# EthernetGCS.net
KiCad netlist of a schematic drawn in EAGLE
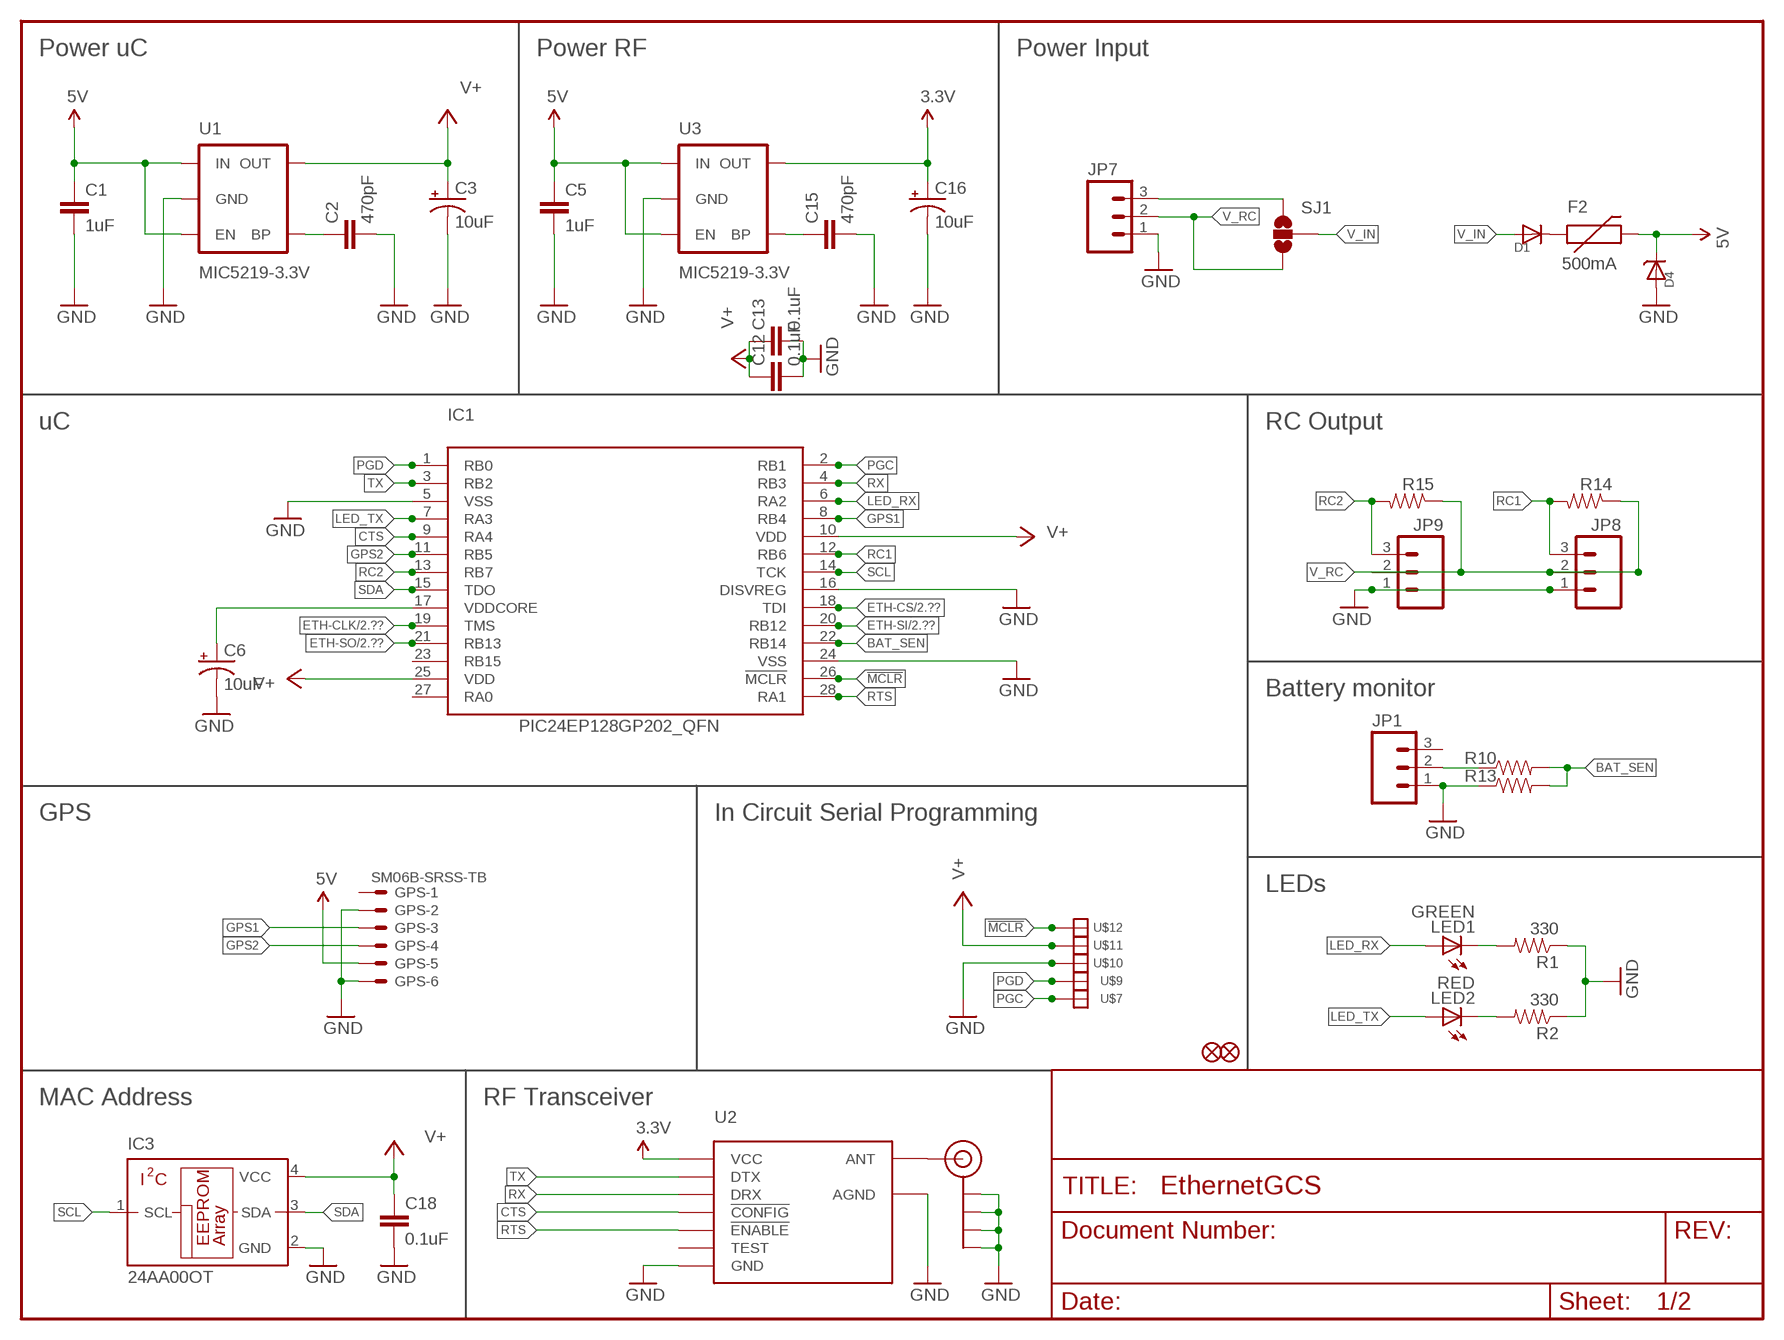
[diagram p0: schematic, sheet 1]
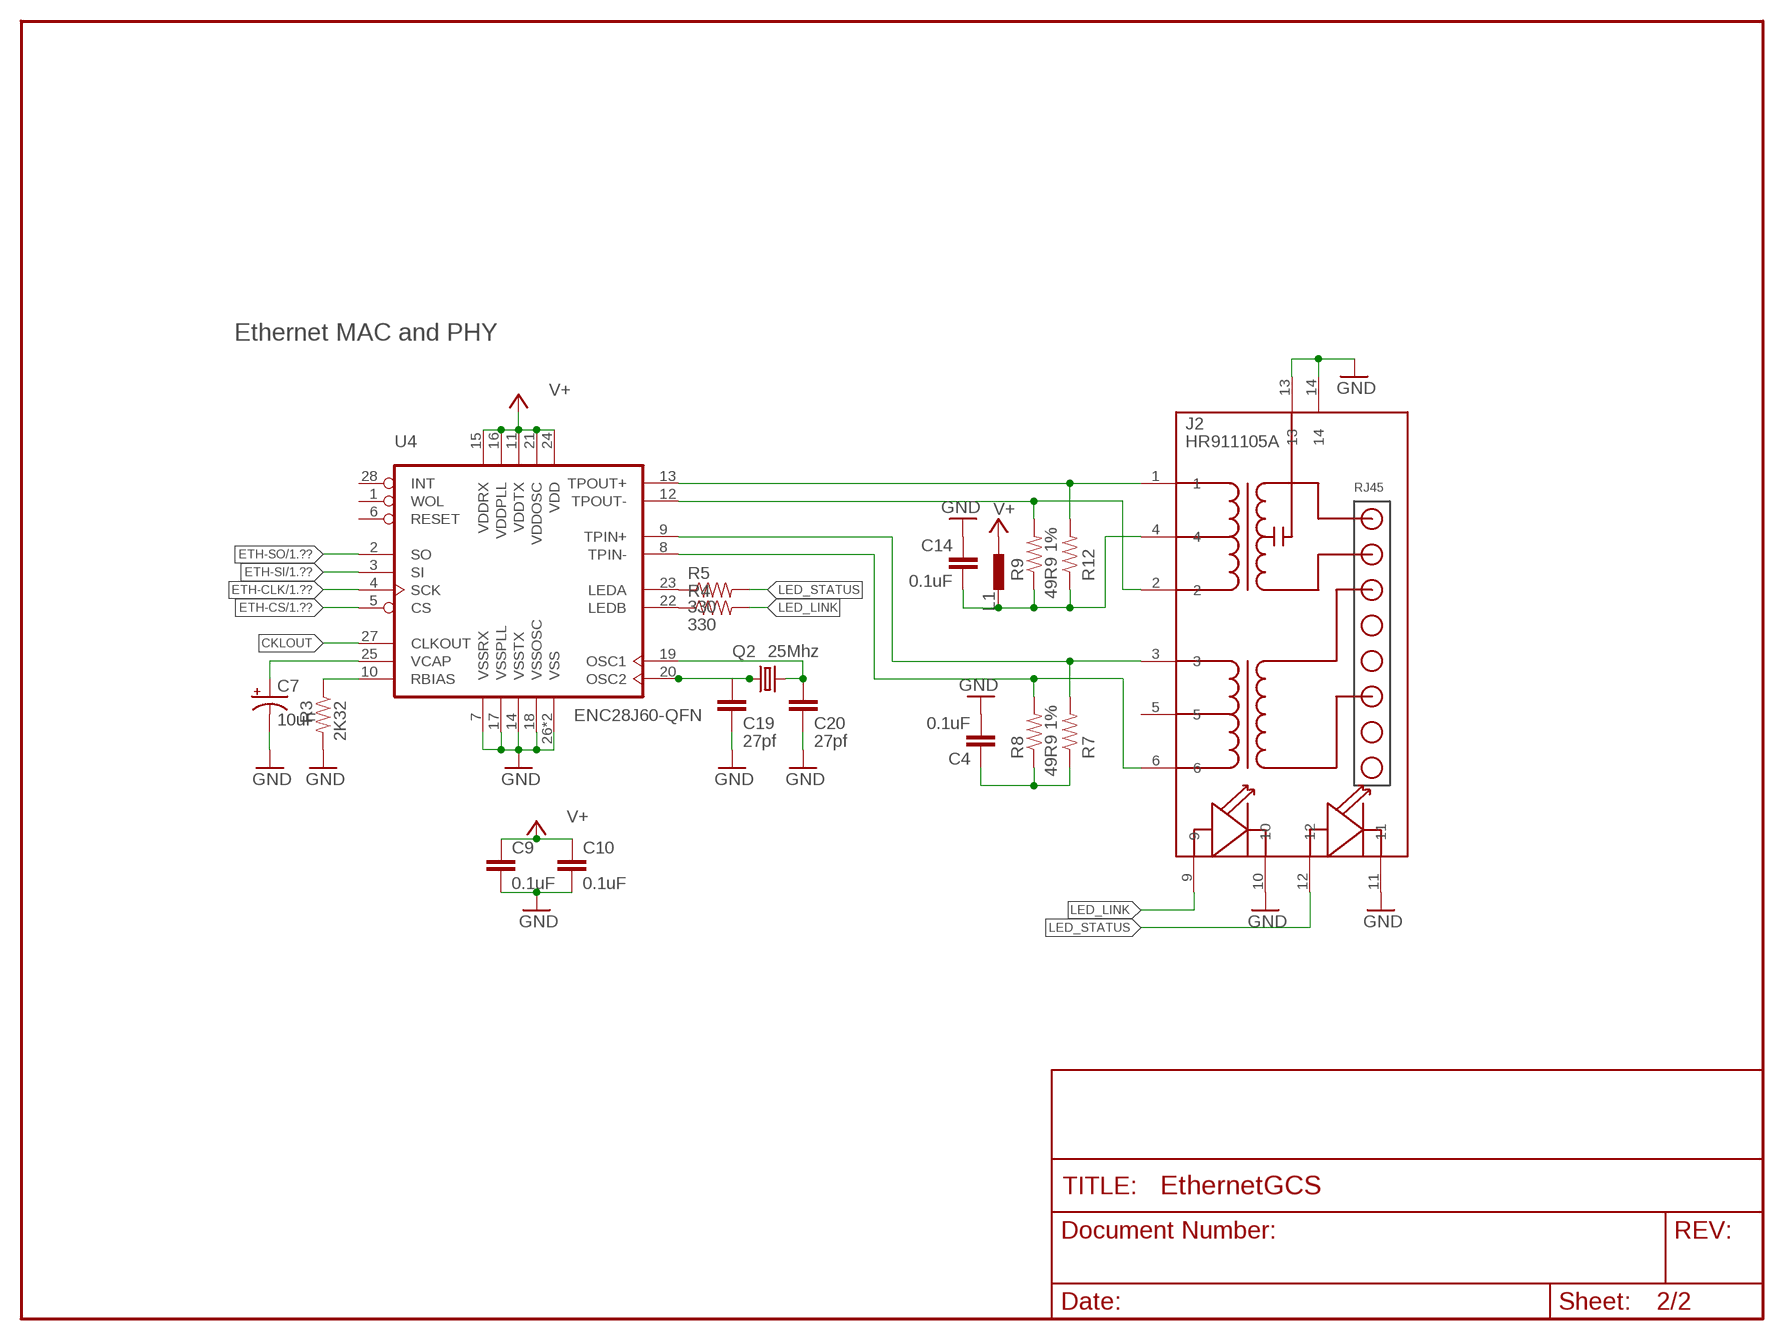
[diagram p1: schematic, sheet 2]

(export (version "E")
  (design (tool "Eeschema 10.0.6"))
  (components
    (comp (ref "C1")
      (value "1uF")
      (footprint "eagle-import:0402-CAP")
      (libsource (lib "eagle-import") (part "CAP0402-CAP"))
    )
    (comp (ref "C2")
      (value "470pF")
      (footprint "eagle-import:0402-CAP")
      (libsource (lib "eagle-import") (part "CAP0402-CAP"))
    )
    (comp (ref "C3")
      (value "10uF")
      (footprint "eagle-import:EIA3216")
      (libsource (lib "eagle-import") (part "CAP_POL1206"))
    )
    (comp (ref "C5")
      (value "1uF")
      (footprint "eagle-import:0402-CAP")
      (libsource (lib "eagle-import") (part "CAP0402-CAP"))
    )
    (comp (ref "C6")
      (value "10uF")
      (footprint "eagle-import:EIA3216")
      (libsource (lib "eagle-import") (part "CAP_POL1206"))
    )
    (comp (ref "C12")
      (value "0.1uF")
      (footprint "eagle-import:0402-CAP")
      (libsource (lib "eagle-import") (part "CAP0402-CAP"))
    )
    (comp (ref "C13")
      (value "0.1uF")
      (footprint "eagle-import:0402-CAP")
      (libsource (lib "eagle-import") (part "CAP0402-CAP"))
    )
    (comp (ref "C15")
      (value "470pF")
      (footprint "eagle-import:0402-CAP")
      (libsource (lib "eagle-import") (part "CAP0402-CAP"))
    )
    (comp (ref "C16")
      (value "10uF")
      (footprint "eagle-import:EIA3216")
      (libsource (lib "eagle-import") (part "CAP_POL1206"))
    )
    (comp (ref "C18")
      (value "0.1uF")
      (footprint "eagle-import:0402-CAP")
      (libsource (lib "eagle-import") (part "CAP0402-CAP"))
    )
    (comp (ref "D1")
      (value "MBR120VLSFT1G")
      (footprint "eagle-import:SOD-123")
      (libsource (lib "eagle-import") (part "DIODESOD-123"))
    )
    (comp (ref "D4")
      (value "MMSZ5233BT1G")
      (footprint "eagle-import:SOD-123")
      (libsource (lib "eagle-import") (part "DIODESOD-123"))
    )
    (comp (ref "F2")
      (value "500mA")
      (footprint "eagle-import:PTC-1206")
      (libsource (lib "eagle-import") (part "PTCSMD"))
    )
    (comp (ref "GPS")
      (value "SM06B-SRSS-TB")
      (footprint "eagle-import:SM06B-SRSS-TB")
      (libsource (lib "eagle-import") (part "?M06B-SRSS-TBS"))
    )
    (comp (ref "IC1")
      (value "PIC24EP128GP202_QFN")
      (footprint "eagle-import:QFN28-ML_6X6MM")
      (fields
        (field (name "MPN") "PIC24FJ64GA002-E/ML")
        (field (name "MPN_1") "PIC24FJ64GA002-E/ML")
        (field (name "OC_FARNELL") "1818728")
        (field (name "OC_NEWARK") "98M1922")
      )
      (libsource (lib "eagle-import") (part "PIC24FJ64GA002_QFN"))
    )
    (comp (ref "IC3")
      (value "24AA00OT")
      (footprint "eagle-import:SOT23-5L")
      (fields (field (name "MF") "MICROCHIP") (field (name "MPN") "24AA00T-I/OTG"))
      (libsource (lib "eagle-import") (part "2400OTAA"))
    )
    (comp (ref "J$1")
      (value "SMA_EDGE")
      (footprint "eagle-import:SMA-EDGE")
      (libsource (lib "eagle-import") (part "SMA_EDGE"))
    )
    (comp (ref "JP1")
      (value "M03PTH")
      (footprint "eagle-import:1X03")
      (libsource (lib "eagle-import") (part "M03PTH"))
    )
    (comp (ref "JP2")
      (value "FIDUCIAL1X2")
      (footprint "eagle-import:FIDUCIAL-1X2")
      (libsource (lib "eagle-import") (part "FIDUCIAL1X2"))
    )
    (comp (ref "JP3")
      (value "FIDUCIAL1X2")
      (footprint "eagle-import:FIDUCIAL-1X2")
      (libsource (lib "eagle-import") (part "FIDUCIAL1X2"))
    )
    (comp (ref "JP7")
      (value "M03PTH")
      (footprint "eagle-import:1X03")
      (libsource (lib "eagle-import") (part "M03PTH"))
    )
    (comp (ref "JP8")
      (value "M03PTH")
      (footprint "eagle-import:1X03")
      (libsource (lib "eagle-import") (part "M03PTH"))
    )
    (comp (ref "JP9")
      (value "M03PTH")
      (footprint "eagle-import:1X03")
      (libsource (lib "eagle-import") (part "M03PTH"))
    )
    (comp (ref "LED1")
      (value "GREEN")
      (footprint "eagle-import:LED-0603")
      (libsource (lib "eagle-import") (part "LED0603"))
    )
    (comp (ref "LED2")
      (value "RED")
      (footprint "eagle-import:LED-0603")
      (libsource (lib "eagle-import") (part "LED0603"))
    )
    (comp (ref "R1")
      (value "330")
      (footprint "eagle-import:0402-RES")
      (libsource (lib "eagle-import") (part "RESISTOR0402-RES"))
    )
    (comp (ref "R2")
      (value "330")
      (footprint "eagle-import:0402-RES")
      (libsource (lib "eagle-import") (part "RESISTOR0402-RES"))
    )
    (comp (ref "R10")
      (value "RESISTOR0402-RES")
      (footprint "eagle-import:0402-RES")
      (libsource (lib "eagle-import") (part "RESISTOR0402-RES"))
    )
    (comp (ref "R13")
      (value "RESISTOR0402-RES")
      (footprint "eagle-import:0402-RES")
      (libsource (lib "eagle-import") (part "RESISTOR0402-RES"))
    )
    (comp (ref "R14")
      (value "RESISTOR0402-RES")
      (footprint "eagle-import:0402-RES")
      (libsource (lib "eagle-import") (part "RESISTOR0402-RES"))
    )
    (comp (ref "R15")
      (value "RESISTOR0402-RES")
      (footprint "eagle-import:0402-RES")
      (libsource (lib "eagle-import") (part "RESISTOR0402-RES"))
    )
    (comp (ref "SJ1")
      (value "SOLDERJUMPER_2WAYT")
      (footprint "eagle-import:SJ_2")
      (libsource (lib "eagle-import") (part "SOLDERJUMPER_2WAYT"))
    )
    (comp (ref "U$7")
      (value "SOLDER_PAD150_75")
      (footprint "eagle-import:SOLD_PAD_150_75")
      (libsource (lib "eagle-import") (part "SOLDER_PAD150_75"))
    )
    (comp (ref "U$9")
      (value "SOLDER_PAD150_75")
      (footprint "eagle-import:SOLD_PAD_150_75")
      (libsource (lib "eagle-import") (part "SOLDER_PAD150_75"))
    )
    (comp (ref "U$10")
      (value "SOLDER_PAD150_75")
      (footprint "eagle-import:SOLD_PAD_150_75")
      (libsource (lib "eagle-import") (part "SOLDER_PAD150_75"))
    )
    (comp (ref "U$11")
      (value "SOLDER_PAD150_75")
      (footprint "eagle-import:SOLD_PAD_150_75")
      (libsource (lib "eagle-import") (part "SOLDER_PAD150_75"))
    )
    (comp (ref "U$12")
      (value "SOLDER_PAD150_75")
      (footprint "eagle-import:SOLD_PAD_150_75")
      (libsource (lib "eagle-import") (part "SOLDER_PAD150_75"))
    )
    (comp (ref "U1")
      (value "MIC5219-3.3V")
      (footprint "eagle-import:SOT23-5")
      (libsource (lib "eagle-import") (part "V_REG_LDOSMD"))
    )
    (comp (ref "U2")
      (value "HM-TRPSMD")
      (footprint "eagle-import:HM-TRP-SMD")
      (libsource (lib "eagle-import") (part "HM-TRPSMD"))
    )
    (comp (ref "U3")
      (value "MIC5219-3.3V")
      (footprint "eagle-import:SOT23-5")
      (libsource (lib "eagle-import") (part "V_REG_LDOSMD"))
    )
    (comp (ref "C4")
      (value "0.1uF")
      (footprint "eagle-import:0402-CAP")
      (libsource (lib "eagle-import") (part "CAP0402-CAP"))
    )
    (comp (ref "C7")
      (value "10uF")
      (footprint "eagle-import:EIA3216")
      (libsource (lib "eagle-import") (part "CAP_POL1206"))
    )
    (comp (ref "C9")
      (value "0.1uF")
      (footprint "eagle-import:0402-CAP")
      (libsource (lib "eagle-import") (part "CAP0402-CAP"))
    )
    (comp (ref "C10")
      (value "0.1uF")
      (footprint "eagle-import:0402-CAP")
      (libsource (lib "eagle-import") (part "CAP0402-CAP"))
    )
    (comp (ref "C14")
      (value "0.1uF")
      (footprint "eagle-import:0402-CAP")
      (libsource (lib "eagle-import") (part "CAP0402-CAP"))
    )
    (comp (ref "C19")
      (value "27pf")
      (footprint "eagle-import:0402-CAP")
      (libsource (lib "eagle-import") (part "CAP0402-CAP"))
    )
    (comp (ref "C20")
      (value "27pf")
      (footprint "eagle-import:0402-CAP")
      (libsource (lib "eagle-import") (part "CAP0402-CAP"))
    )
    (comp (ref "J2")
      (value "HR911105A")
      (footprint "eagle-import:HR911105A")
      (libsource (lib "eagle-import") (part "HR911105A"))
    )
    (comp (ref "L1")
      (value "BLM15HD102SN1")
      (footprint "eagle-import:0402-IND")
      (libsource (lib "eagle-import") (part "INDUCTOR-0402"))
    )
    (comp (ref "Q2")
      (value "25Mhz")
      (footprint "eagle-import:CTS406")
      (libsource (lib "eagle-import") (part "CRYSTALCTS406"))
    )
    (comp (ref "R3")
      (value "2K32")
      (footprint "eagle-import:0402-RES")
      (libsource (lib "eagle-import") (part "RESISTOR0402-RES"))
    )
    (comp (ref "R4")
      (value "330")
      (footprint "eagle-import:0402-RES")
      (libsource (lib "eagle-import") (part "RESISTOR0402-RES"))
    )
    (comp (ref "R5")
      (value "330")
      (footprint "eagle-import:0402-RES")
      (libsource (lib "eagle-import") (part "RESISTOR0402-RES"))
    )
    (comp (ref "R7")
      (value "49R9 1%")
      (footprint "eagle-import:0402-RES")
      (libsource (lib "eagle-import") (part "RESISTOR0402-RES"))
    )
    (comp (ref "R8")
      (value "49R9 1%")
      (footprint "eagle-import:0402-RES")
      (libsource (lib "eagle-import") (part "RESISTOR0402-RES"))
    )
    (comp (ref "R9")
      (value "49R9 1%")
      (footprint "eagle-import:0402-RES")
      (libsource (lib "eagle-import") (part "RESISTOR0402-RES"))
    )
    (comp (ref "R12")
      (value "49R9 1%")
      (footprint "eagle-import:0402-RES")
      (libsource (lib "eagle-import") (part "RESISTOR0402-RES"))
    )
    (comp (ref "U4")
      (value "ENC28J60-QFN")
      (footprint "eagle-import:QFN28")
      (libsource (lib "eagle-import") (part "ENC28J60-QFN"))
    )
  )
  (nets
    (net (code "1") (name "3.3V") (class "Default")
      (node (ref "C16") (pin "A") (pinfunction "+_A") (pintype "passive"))
      (node (ref "U2") (pin "VCC") (pinfunction "VCC_VCC") (pintype "power_in"))
      (node (ref "U3") (pin "5") (pinfunction "OUT_5") (pintype "passive"))
    )
    (net (code "2") (name "5V") (class "Default")
      (node (ref "C1") (pin "1") (pinfunction "1_1") (pintype "passive"))
      (node (ref "C5") (pin "1") (pinfunction "1_1") (pintype "passive"))
      (node (ref "D4") (pin "C") (pinfunction "C_C") (pintype "passive"))
      (node (ref "F2") (pin "2") (pinfunction "2_2") (pintype "bidirectional"))
      (node (ref "GPS") (pin "5") (pinfunction "S_5") (pintype "passive"))
      (node (ref "U1") (pin "1") (pinfunction "IN_1") (pintype "input"))
      (node (ref "U1") (pin "3") (pinfunction "EN_3") (pintype "input"))
      (node (ref "U3") (pin "1") (pinfunction "IN_1") (pintype "input"))
      (node (ref "U3") (pin "3") (pinfunction "EN_3") (pintype "input"))
    )
    (net (code "3") (name "BAT_SEN") (class "Default")
      (node (ref "IC1") (pin "22") (pinfunction "RB14_22") (pintype "bidirectional"))
      (node (ref "R10") (pin "2") (pinfunction "2_2") (pintype "passive"))
      (node (ref "R13") (pin "2") (pinfunction "2_2") (pintype "passive"))
    )
    (net (code "4") (name "CKLOUT") (class "Default")
      (node (ref "U4") (pin "27") (pinfunction "CLKOUT_27") (pintype "output"))
    )
    (net (code "5") (name "CTS") (class "Default")
      (node (ref "IC1") (pin "9") (pinfunction "RA4_9") (pintype "bidirectional"))
      (node (ref "U2") (pin "!CONFIG") (pinfunction "~{CONFIG}_!CONFIG") (pintype "input"))
    )
    (net (code "6") (name "ETH-CLK") (class "Default")
      (node (ref "IC1") (pin "19") (pinfunction "TMS_19") (pintype "input"))
      (node (ref "U4") (pin "4") (pinfunction "SCK_4") (pintype "input"))
    )
    (net (code "7") (name "ETH-CS") (class "Default")
      (node (ref "IC1") (pin "18") (pinfunction "TDI_18") (pintype "input"))
      (node (ref "U4") (pin "5") (pinfunction "CS_5") (pintype "input"))
    )
    (net (code "8") (name "ETH-SI") (class "Default")
      (node (ref "IC1") (pin "20") (pinfunction "RB12_20") (pintype "bidirectional"))
      (node (ref "U4") (pin "3") (pinfunction "SI_3") (pintype "input"))
    )
    (net (code "9") (name "ETH-SO") (class "Default")
      (node (ref "IC1") (pin "21") (pinfunction "RB13_21") (pintype "bidirectional"))
      (node (ref "U4") (pin "2") (pinfunction "SO_2") (pintype "output"))
    )
    (net (code "10") (name "GND") (class "Default")
      (node (ref "C1") (pin "2") (pinfunction "2_2") (pintype "passive"))
      (node (ref "C10") (pin "2") (pinfunction "2_2") (pintype "passive"))
      (node (ref "C12") (pin "2") (pinfunction "2_2") (pintype "passive"))
      (node (ref "C13") (pin "2") (pinfunction "2_2") (pintype "passive"))
      (node (ref "C14") (pin "1") (pinfunction "1_1") (pintype "passive"))
      (node (ref "C15") (pin "2") (pinfunction "2_2") (pintype "passive"))
      (node (ref "C16") (pin "C") (pinfunction "-_C") (pintype "passive"))
      (node (ref "C18") (pin "2") (pinfunction "2_2") (pintype "passive"))
      (node (ref "C19") (pin "2") (pinfunction "2_2") (pintype "passive"))
      (node (ref "C2") (pin "2") (pinfunction "2_2") (pintype "passive"))
      (node (ref "C20") (pin "2") (pinfunction "2_2") (pintype "passive"))
      (node (ref "C3") (pin "C") (pinfunction "-_C") (pintype "passive"))
      (node (ref "C4") (pin "2") (pinfunction "2_2") (pintype "passive"))
      (node (ref "C5") (pin "2") (pinfunction "2_2") (pintype "passive"))
      (node (ref "C6") (pin "C") (pinfunction "-_C") (pintype "passive"))
      (node (ref "C7") (pin "C") (pinfunction "-_C") (pintype "passive"))
      (node (ref "C9") (pin "2") (pinfunction "2_2") (pintype "passive"))
      (node (ref "D4") (pin "A") (pinfunction "A_A") (pintype "passive"))
      (node (ref "GPS") (pin "2") (pinfunction "S_2") (pintype "passive"))
      (node (ref "GPS") (pin "6") (pinfunction "S_6") (pintype "passive"))
      (node (ref "IC1") (pin "16") (pinfunction "DISVREG_16") (pintype "passive"))
      (node (ref "IC1") (pin "24") (pinfunction "VSS_24") (pintype "power_in"))
      (node (ref "IC1") (pin "5") (pinfunction "VSS_5") (pintype "power_in"))
      (node (ref "IC3") (pin "2") (pinfunction "GND_2") (pintype "power_in"))
      (node (ref "J$1") (pin "GND@0") (pinfunction "GND_GND@0") (pintype "bidirectional"))
      (node (ref "J$1") (pin "GND@1") (pinfunction "GND_GND@1") (pintype "bidirectional"))
      (node (ref "J$1") (pin "GND@2") (pinfunction "GND_GND@2") (pintype "bidirectional"))
      (node (ref "J$1") (pin "GND@3") (pinfunction "GND_GND@3") (pintype "bidirectional"))
      (node (ref "J2") (pin "10") (pinfunction "10_10") (pintype "bidirectional"))
      (node (ref "J2") (pin "11") (pinfunction "11_11") (pintype "bidirectional"))
      (node (ref "J2") (pin "13") (pinfunction "13_13") (pintype "bidirectional"))
      (node (ref "J2") (pin "14") (pinfunction "14_14") (pintype "bidirectional"))
      (node (ref "JP1") (pin "1") (pinfunction "1_1") (pintype "passive"))
      (node (ref "JP7") (pin "1") (pinfunction "1_1") (pintype "passive"))
      (node (ref "JP8") (pin "1") (pinfunction "1_1") (pintype "passive"))
      (node (ref "JP9") (pin "1") (pinfunction "1_1") (pintype "passive"))
      (node (ref "R1") (pin "1") (pinfunction "1_1") (pintype "passive"))
      (node (ref "R13") (pin "1") (pinfunction "1_1") (pintype "passive"))
      (node (ref "R2") (pin "1") (pinfunction "1_1") (pintype "passive"))
      (node (ref "R3") (pin "2") (pinfunction "2_2") (pintype "passive"))
      (node (ref "U$10") (pin "P$1") (pinfunction "P$1_P$1") (pintype "bidirectional"))
      (node (ref "U1") (pin "2") (pinfunction "GND_2") (pintype "input"))
      (node (ref "U2") (pin "AGND") (pinfunction "AGND_AGND") (pintype "power_in"))
      (node (ref "U2") (pin "GND") (pinfunction "GND_GND") (pintype "power_in"))
      (node (ref "U3") (pin "2") (pinfunction "GND_2") (pintype "input"))
      (node (ref "U4") (pin "14") (pinfunction "VSSTX_14") (pintype "power_in"))
      (node (ref "U4") (pin "17") (pinfunction "VSSPLL_17") (pintype "power_in"))
      (node (ref "U4") (pin "18") (pinfunction "VSSOSC_18") (pintype "power_in"))
      (node (ref "U4") (pin "26") (pinfunction "VSS_26") (pintype "power_in"))
      (node (ref "U4") (pin "7") (pinfunction "VSSRX_7") (pintype "power_in"))
      (node (ref "U4") (pin "EXP") (pinfunction "VSS_EXP") (pintype "power_in"))
    )
    (net (code "11") (name "GPS1") (class "Default")
      (node (ref "GPS") (pin "3") (pinfunction "S_3") (pintype "passive"))
      (node (ref "IC1") (pin "8") (pinfunction "RB4_8") (pintype "bidirectional"))
    )
    (net (code "12") (name "GPS2") (class "Default")
      (node (ref "GPS") (pin "4") (pinfunction "S_4") (pintype "passive"))
      (node (ref "IC1") (pin "11") (pinfunction "RB5_11") (pintype "bidirectional"))
    )
    (net (code "13") (name "LED_LINK") (class "Default")
      (node (ref "J2") (pin "9") (pinfunction "9_9") (pintype "bidirectional"))
      (node (ref "R4") (pin "2") (pinfunction "2_2") (pintype "passive"))
    )
    (net (code "14") (name "LED_RX") (class "Default")
      (node (ref "IC1") (pin "6") (pinfunction "RA2_6") (pintype "bidirectional"))
      (node (ref "LED1") (pin "A") (pinfunction "A_A") (pintype "passive"))
    )
    (net (code "15") (name "LED_STATUS") (class "Default")
      (node (ref "J2") (pin "12") (pinfunction "12_12") (pintype "bidirectional"))
      (node (ref "R5") (pin "2") (pinfunction "2_2") (pintype "passive"))
    )
    (net (code "16") (name "LED_TX") (class "Default")
      (node (ref "IC1") (pin "7") (pinfunction "RA3_7") (pintype "bidirectional"))
      (node (ref "LED2") (pin "A") (pinfunction "A_A") (pintype "passive"))
    )
    (net (code "17") (name "Net-(C4-Pad1)") (class "Default")
      (node (ref "C4") (pin "1") (pinfunction "1_1") (pintype "passive"))
      (node (ref "R7") (pin "1") (pinfunction "1_1") (pintype "passive"))
      (node (ref "R8") (pin "1") (pinfunction "1_1") (pintype "passive"))
    )
    (net (code "18") (name "Net-(C6-+)") (class "Default")
      (node (ref "C6") (pin "A") (pinfunction "+_A") (pintype "passive"))
      (node (ref "IC1") (pin "17") (pinfunction "VDDCORE_17") (pintype "power_in"))
    )
    (net (code "19") (name "Net-(C7-+)") (class "Default")
      (node (ref "C7") (pin "A") (pinfunction "+_A") (pintype "passive"))
      (node (ref "U4") (pin "25") (pinfunction "VCAP_25") (pintype "power_in"))
    )
    (net (code "20") (name "Net-(D1-PadC)") (class "Default")
      (node (ref "D1") (pin "C") (pinfunction "C_C") (pintype "passive"))
      (node (ref "F2") (pin "1") (pinfunction "1_1") (pintype "bidirectional"))
    )
    (net (code "21") (name "Net-(J$1-SIGNAL)") (class "Default")
      (node (ref "J$1") (pin "SIG") (pinfunction "SIGNAL_SIG") (pintype "bidirectional"))
      (node (ref "U2") (pin "ANT") (pinfunction "ANT_ANT") (pintype "bidirectional"))
    )
    (net (code "22") (name "Net-(JP1-Pad2)") (class "Default")
      (node (ref "JP1") (pin "2") (pinfunction "2_2") (pintype "passive"))
      (node (ref "R10") (pin "1") (pinfunction "1_1") (pintype "passive"))
    )
    (net (code "23") (name "Net-(JP7-Pad3)") (class "Default")
      (node (ref "JP7") (pin "3") (pinfunction "3_3") (pintype "passive"))
      (node (ref "SJ1") (pin "3") (pinfunction "3_3") (pintype "passive"))
    )
    (net (code "24") (name "Net-(L1-1)") (class "Default")
      (node (ref "C14") (pin "2") (pinfunction "2_2") (pintype "passive"))
      (node (ref "J2") (pin "4") (pinfunction "4_4") (pintype "bidirectional"))
      (node (ref "L1") (pin "P$1") (pinfunction "1_P$1") (pintype "passive"))
      (node (ref "R12") (pin "1") (pinfunction "1_1") (pintype "passive"))
      (node (ref "R9") (pin "1") (pinfunction "1_1") (pintype "passive"))
    )
    (net (code "25") (name "Net-(LED1-PadC)") (class "Default")
      (node (ref "LED1") (pin "C") (pinfunction "C_C") (pintype "passive"))
      (node (ref "R1") (pin "2") (pinfunction "2_2") (pintype "passive"))
    )
    (net (code "26") (name "Net-(LED2-PadC)") (class "Default")
      (node (ref "LED2") (pin "C") (pinfunction "C_C") (pintype "passive"))
      (node (ref "R2") (pin "2") (pinfunction "2_2") (pintype "passive"))
    )
    (net (code "27") (name "Net-(Q2-2)") (class "Default")
      (node (ref "C20") (pin "1") (pinfunction "1_1") (pintype "passive"))
      (node (ref "Q2") (pin "3") (pinfunction "2_3") (pintype "passive"))
      (node (ref "U4") (pin "19") (pinfunction "OSC1_19") (pintype "input"))
    )
    (net (code "28") (name "Net-(U1-BP)") (class "Default")
      (node (ref "C2") (pin "1") (pinfunction "1_1") (pintype "passive"))
      (node (ref "U1") (pin "4") (pinfunction "BP_4") (pintype "input"))
    )
    (net (code "29") (name "Net-(U3-BP)") (class "Default")
      (node (ref "C15") (pin "1") (pinfunction "1_1") (pintype "passive"))
      (node (ref "U3") (pin "4") (pinfunction "BP_4") (pintype "input"))
    )
    (net (code "30") (name "Net-(U4-LEDA)") (class "Default")
      (node (ref "R5") (pin "1") (pinfunction "1_1") (pintype "passive"))
      (node (ref "U4") (pin "23") (pinfunction "LEDA_23") (pintype "output"))
    )
    (net (code "31") (name "Net-(U4-LEDB)") (class "Default")
      (node (ref "R4") (pin "1") (pinfunction "1_1") (pintype "passive"))
      (node (ref "U4") (pin "22") (pinfunction "LEDB_22") (pintype "output"))
    )
    (net (code "32") (name "Net-(U4-OSC2)") (class "Default")
      (node (ref "C19") (pin "1") (pinfunction "1_1") (pintype "passive"))
      (node (ref "Q2") (pin "1") (pinfunction "1_1") (pintype "passive"))
      (node (ref "U4") (pin "20") (pinfunction "OSC2_20") (pintype "output"))
    )
    (net (code "33") (name "Net-(U4-RBIAS)") (class "Default")
      (node (ref "R3") (pin "1") (pinfunction "1_1") (pintype "passive"))
      (node (ref "U4") (pin "10") (pinfunction "RBIAS_10") (pintype "passive"))
    )
    (net (code "34") (name "Net-(U4-TPIN+)") (class "Default")
      (node (ref "J2") (pin "3") (pinfunction "3_3") (pintype "bidirectional"))
      (node (ref "R7") (pin "2") (pinfunction "2_2") (pintype "passive"))
      (node (ref "U4") (pin "9") (pinfunction "TPIN+_9") (pintype "input"))
    )
    (net (code "35") (name "Net-(U4-TPIN-)") (class "Default")
      (node (ref "J2") (pin "6") (pinfunction "6_6") (pintype "bidirectional"))
      (node (ref "R8") (pin "2") (pinfunction "2_2") (pintype "passive"))
      (node (ref "U4") (pin "8") (pinfunction "TPIN-_8") (pintype "input"))
    )
    (net (code "36") (name "Net-(U4-TPOUT+)") (class "Default")
      (node (ref "J2") (pin "1") (pinfunction "1_1") (pintype "bidirectional"))
      (node (ref "R12") (pin "2") (pinfunction "2_2") (pintype "passive"))
      (node (ref "U4") (pin "13") (pinfunction "TPOUT+_13") (pintype "output"))
    )
    (net (code "37") (name "Net-(U4-TPOUT-)") (class "Default")
      (node (ref "J2") (pin "2") (pinfunction "2_2") (pintype "bidirectional"))
      (node (ref "R9") (pin "2") (pinfunction "2_2") (pintype "passive"))
      (node (ref "U4") (pin "12") (pinfunction "TPOUT-_12") (pintype "output"))
    )
    (net (code "38") (name "PGC") (class "Default")
      (node (ref "IC1") (pin "2") (pinfunction "RB1_2") (pintype "bidirectional"))
      (node (ref "U$7") (pin "P$1") (pinfunction "P$1_P$1") (pintype "bidirectional"))
    )
    (net (code "39") (name "PGD") (class "Default")
      (node (ref "IC1") (pin "1") (pinfunction "RB0_1") (pintype "bidirectional"))
      (node (ref "U$9") (pin "P$1") (pinfunction "P$1_P$1") (pintype "bidirectional"))
    )
    (net (code "40") (name "RC1") (class "Default")
      (node (ref "IC1") (pin "12") (pinfunction "RB6_12") (pintype "bidirectional"))
      (node (ref "JP8") (pin "3") (pinfunction "3_3") (pintype "passive"))
      (node (ref "R14") (pin "2") (pinfunction "2_2") (pintype "passive"))
    )
    (net (code "41") (name "RC2") (class "Default")
      (node (ref "IC1") (pin "13") (pinfunction "RB7_13") (pintype "bidirectional"))
      (node (ref "JP9") (pin "3") (pinfunction "3_3") (pintype "passive"))
      (node (ref "R15") (pin "2") (pinfunction "2_2") (pintype "passive"))
    )
    (net (code "42") (name "RTS") (class "Default")
      (node (ref "IC1") (pin "28") (pinfunction "RA1_28") (pintype "bidirectional"))
      (node (ref "U2") (pin "!ENABLE") (pinfunction "~{ENABLE}_!ENABLE") (pintype "input"))
    )
    (net (code "43") (name "RX") (class "Default")
      (node (ref "IC1") (pin "4") (pinfunction "RB3_4") (pintype "bidirectional"))
      (node (ref "U2") (pin "DRX") (pinfunction "DRX_DRX") (pintype "input"))
    )
    (net (code "44") (name "SCL") (class "Default")
      (node (ref "IC1") (pin "14") (pinfunction "TCK_14") (pintype "input"))
      (node (ref "IC3") (pin "1") (pinfunction "SCL_1") (pintype "input"))
    )
    (net (code "45") (name "SDA") (class "Default")
      (node (ref "IC1") (pin "15") (pinfunction "TDO_15") (pintype "output"))
      (node (ref "IC3") (pin "3") (pinfunction "SDA_3") (pintype "bidirectional"))
    )
    (net (code "46") (name "TX") (class "Default")
      (node (ref "IC1") (pin "3") (pinfunction "RB2_3") (pintype "bidirectional"))
      (node (ref "U2") (pin "DTX") (pinfunction "DTX_DTX") (pintype "output"))
    )
    (net (code "47") (name "V+") (class "Default")
      (node (ref "C10") (pin "1") (pinfunction "1_1") (pintype "passive"))
      (node (ref "C12") (pin "1") (pinfunction "1_1") (pintype "passive"))
      (node (ref "C13") (pin "1") (pinfunction "1_1") (pintype "passive"))
      (node (ref "C18") (pin "1") (pinfunction "1_1") (pintype "passive"))
      (node (ref "C3") (pin "A") (pinfunction "+_A") (pintype "passive"))
      (node (ref "C9") (pin "1") (pinfunction "1_1") (pintype "passive"))
      (node (ref "IC1") (pin "10") (pinfunction "VDD_10") (pintype "power_in"))
      (node (ref "IC1") (pin "25") (pinfunction "VDD_25") (pintype "power_in"))
      (node (ref "IC3") (pin "4") (pinfunction "VCC_4") (pintype "power_in"))
      (node (ref "L1") (pin "P$2") (pinfunction "2_P$2") (pintype "passive"))
      (node (ref "U$11") (pin "P$1") (pinfunction "P$1_P$1") (pintype "bidirectional"))
      (node (ref "U1") (pin "5") (pinfunction "OUT_5") (pintype "passive"))
      (node (ref "U4") (pin "11") (pinfunction "VDDTX_11") (pintype "power_in"))
      (node (ref "U4") (pin "15") (pinfunction "VDDRX_15") (pintype "power_in"))
      (node (ref "U4") (pin "16") (pinfunction "VDDPLL_16") (pintype "power_in"))
      (node (ref "U4") (pin "21") (pinfunction "VDDOSC_21") (pintype "power_in"))
      (node (ref "U4") (pin "24") (pinfunction "VDD_24") (pintype "power_in"))
    )
    (net (code "48") (name "V_IN") (class "Default")
      (node (ref "D1") (pin "A") (pinfunction "A_A") (pintype "passive"))
      (node (ref "SJ1") (pin "2") (pinfunction "2_2") (pintype "passive"))
    )
    (net (code "49") (name "V_RC") (class "Default")
      (node (ref "JP7") (pin "2") (pinfunction "2_2") (pintype "passive"))
      (node (ref "JP8") (pin "2") (pinfunction "2_2") (pintype "passive"))
      (node (ref "JP9") (pin "2") (pinfunction "2_2") (pintype "passive"))
      (node (ref "R14") (pin "1") (pinfunction "1_1") (pintype "passive"))
      (node (ref "R15") (pin "1") (pinfunction "1_1") (pintype "passive"))
      (node (ref "SJ1") (pin "1") (pinfunction "1_1") (pintype "passive"))
    )
    (net (code "50") (name "unconnected-(GPSA-S-Pad1)") (class "Default")
      (node (ref "GPS") (pin "1") (pinfunction "S_1") (pintype "passive"))
    )
    (net (code "51") (name "unconnected-(IC1-RA0-Pad27)") (class "Default")
      (node (ref "IC1") (pin "27") (pinfunction "RA0_27") (pintype "bidirectional"))
    )
    (net (code "52") (name "unconnected-(IC1-RB15-Pad23)") (class "Default")
      (node (ref "IC1") (pin "23") (pinfunction "RB15_23") (pintype "bidirectional"))
    )
    (net (code "53") (name "unconnected-(J2-Pad5)") (class "Default")
      (node (ref "J2") (pin "5") (pinfunction "5_5") (pintype "bidirectional"))
    )
    (net (code "54") (name "unconnected-(JP1-Pad3)") (class "Default")
      (node (ref "JP1") (pin "3") (pinfunction "3_3") (pintype "passive"))
    )
    (net (code "55") (name "unconnected-(U2-PadTEST)") (class "Default")
      (node (ref "U2") (pin "TEST") (pinfunction "TEST_TEST") (pintype "no_connect"))
    )
    (net (code "56") (name "unconnected-(U4-INT-Pad28)") (class "Default")
      (node (ref "U4") (pin "28") (pinfunction "INT_28") (pintype "output"))
    )
    (net (code "57") (name "unconnected-(U4-RESET-Pad6)") (class "Default")
      (node (ref "U4") (pin "6") (pinfunction "RESET_6") (pintype "input"))
    )
    (net (code "58") (name "unconnected-(U4-WOL-Pad1)") (class "Default")
      (node (ref "U4") (pin "1") (pinfunction "WOL_1") (pintype "output"))
    )
    (net (code "59") (name "~{MCLR}") (class "Default")
      (node (ref "IC1") (pin "26") (pinfunction "~{MCLR}_26") (pintype "bidirectional"))
      (node (ref "U$12") (pin "P$1") (pinfunction "P$1_P$1") (pintype "bidirectional"))
    )
  )
)
